# F_IN_CKT.net
KiCad netlist of a schematic drawn in Altium Designer
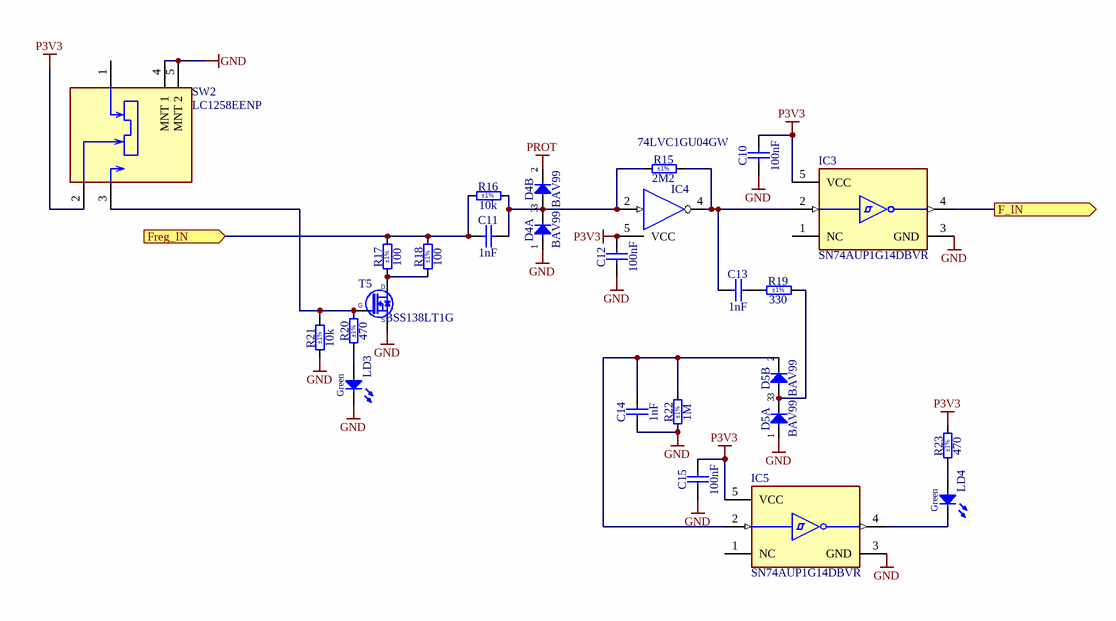
[diagram p0: F_IN_CKT.SchDoc]

(export (version "E")
  (design (tool "Eeschema 10.0.6"))
  (components
    (comp (ref "C10")
      (value "100nF")
      (footprint "CAPC1608X90N")
      (description "Non-polarised capacitor")
      (fields
        (field (name "PART NUMBER") "CC0603_100NF_100V_10%_X7R")
        (field (name "VOLTAGE") "100V")
        (field (name "AUTHOR") "CERN DEM JLC")
      )
      (libsource (lib "Capacitors") (part "Capacitor - non polarized"))
    )
    (comp (ref "C11")
      (value "1nF")
      (footprint "CAPC1608X90N")
      (description "Non-polarised capacitor")
      (fields
        (field (name "PART NUMBER") "CC0603_1NF_50V_1%_NP0")
        (field (name "VOLTAGE") "50V")
        (field (name "AUTHOR") "CERN DEM JLC")
      )
      (libsource (lib "Capacitors") (part "Capacitor - non polarized"))
    )
    (comp (ref "C12")
      (value "100nF")
      (footprint "CAPC1608X90N")
      (description "Non-polarised capacitor")
      (fields
        (field (name "PART NUMBER") "CC0603_100NF_100V_10%_X7R")
        (field (name "VOLTAGE") "100V")
        (field (name "AUTHOR") "CERN DEM JLC")
      )
      (libsource (lib "Capacitors") (part "Capacitor - non polarized"))
    )
    (comp (ref "C13")
      (value "1nF")
      (footprint "CAPC1608X90N")
      (description "Non-polarised capacitor")
      (fields
        (field (name "PART NUMBER") "CC0603_1NF_50V_1%_NP0")
        (field (name "VOLTAGE") "50V")
        (field (name "AUTHOR") "CERN DEM JLC")
      )
      (libsource (lib "Capacitors") (part "Capacitor - non polarized"))
    )
    (comp (ref "C14")
      (value "1nF")
      (footprint "CAPC1608X90N")
      (description "Non-polarised capacitor")
      (fields
        (field (name "PART NUMBER") "CC0603_1NF_50V_1%_NP0")
        (field (name "VOLTAGE") "50V")
        (field (name "AUTHOR") "CERN DEM JLC")
      )
      (libsource (lib "Capacitors") (part "Capacitor - non polarized"))
    )
    (comp (ref "C15")
      (value "100nF")
      (footprint "CAPC1608X90N")
      (description "Non-polarised capacitor")
      (fields
        (field (name "PART NUMBER") "CC0603_100NF_100V_10%_X7R")
        (field (name "VOLTAGE") "100V")
        (field (name "AUTHOR") "CERN DEM JLC")
      )
      (libsource (lib "Capacitors") (part "Capacitor - non polarized"))
    )
    (comp (ref "D4")
      (value "BAV99")
      (footprint "SOT95P240X110-3N")
      (description "Serial Diode")
      (fields
        (field (name "VOLTAGE") "70V")
        (field (name "POWER") "350mW")
        (field (name "AUTHOR") "CERN DEM JLC")
      )
      (libsource (lib "ICs And Semiconductors") (part "Diode x2 A1C3_A3C2"))
    )
    (comp (ref "D5")
      (value "BAV99")
      (footprint "SOT95P240X110-3N")
      (description "Serial Diode")
      (fields
        (field (name "VOLTAGE") "70V")
        (field (name "POWER") "350mW")
        (field (name "AUTHOR") "CERN DEM JLC")
      )
      (libsource (lib "ICs And Semiconductors") (part "Diode x2 A1C3_A3C2"))
    )
    (comp (ref "IC3")
      (value "SN74AUP1G14DBVR")
      (footprint "FP-DBV0005A-IPC_A")
      (description "IC INVERTER SCHMITT 1CH SOT23-5")
      (libsource (lib "Altium Content Vault") (part "d7d47fafed669226aeca1918140c228"))
    )
    (comp (ref "IC4")
      (value "74LVC1GU04GW")
      (footprint "SOT65P212X110-5N")
      (description "Single Inverter Buffer")
      (fields (field (name "MANUFACTURER") "NXP SEMICONDUCTORS") (field (name "AUTHOR") "CERN DEM JLC"))
      (libsource (lib "ICs And Semiconductors") (part "741G04"))
    )
    (comp (ref "IC5")
      (value "SN74AUP1G14DBVR")
      (footprint "FP-DBV0005A-IPC_A")
      (description "IC INVERTER SCHMITT 1CH SOT23-5")
      (libsource (lib "Altium Content Vault") (part "d7d47fafed669226aeca1918140c228"))
    )
    (comp (ref "LD3")
      (value "Green")
      (footprint "LED_AVAGO_HSME-C110")
      (description "LED Green 1C 2A")
      (fields
        (field (name "PART NUMBER") "LED_AVAGO_HSME-C110")
        (field (name "MANUFACTURER") "AVAGO TECHNOLOGIES")
        (field (name "AUTHOR") "CERN DEM JMW")
      )
      (libsource (lib "ICs And Semiconductors") (part "LED Green 1C 2A"))
    )
    (comp (ref "LD4")
      (value "Green")
      (footprint "LED_AVAGO_HSME-C110")
      (description "LED Green 1C 2A")
      (fields
        (field (name "PART NUMBER") "LED_AVAGO_HSME-C110")
        (field (name "MANUFACTURER") "AVAGO TECHNOLOGIES")
        (field (name "AUTHOR") "CERN DEM JMW")
      )
      (libsource (lib "ICs And Semiconductors") (part "LED Green 1C 2A"))
    )
    (comp (ref "R15")
      (value "2M2")
      (footprint "RESC1608X55N")
      (description "Resistor - 1%")
      (fields
        (field (name "TOLERANCE") "±1%")
        (field (name "PART NUMBER") "R0603_2M2_1%_0.1W_100PPM")
        (field (name "POWER") "0.1W")
        (field (name "AUTHOR") "CERN DEM JLC")
      )
      (libsource (lib "Resistors") (part "Resistor - 1%"))
    )
    (comp (ref "R16")
      (value "10k")
      (footprint "RESC1608X55N")
      (description "Resistor - 1%")
      (fields
        (field (name "TOLERANCE") "±1%")
        (field (name "PART NUMBER") "R0603_10K_1%_0.1W_100PPM")
        (field (name "POWER") "0.1W")
        (field (name "AUTHOR") "CERN DEM JLC")
      )
      (libsource (lib "Resistors") (part "Resistor - 1%"))
    )
    (comp (ref "R17")
      (value "100")
      (footprint "RESC1608X55N")
      (description "Resistor - 1%")
      (fields
        (field (name "TOLERANCE") "±1%")
        (field (name "PART NUMBER") "R0603_100R_1%_0.1W_100PPM")
        (field (name "POWER") "0.1W")
        (field (name "AUTHOR") "CERN DEM JLC")
      )
      (libsource (lib "Resistors") (part "Resistor - 1%"))
    )
    (comp (ref "R18")
      (value "100")
      (footprint "RESC1608X55N")
      (description "Resistor - 1%")
      (fields
        (field (name "TOLERANCE") "±1%")
        (field (name "PART NUMBER") "R0603_100R_1%_0.1W_100PPM")
        (field (name "POWER") "0.1W")
        (field (name "AUTHOR") "CERN DEM JLC")
      )
      (libsource (lib "Resistors") (part "Resistor - 1%"))
    )
    (comp (ref "R19")
      (value "330")
      (footprint "RESC1608X55N")
      (description "Resistor - 1%")
      (fields
        (field (name "TOLERANCE") "±1%")
        (field (name "PART NUMBER") "R0603_330R_1%_0.1W_100PPM")
        (field (name "POWER") "0.1W")
        (field (name "AUTHOR") "CERN DEM JLC")
      )
      (libsource (lib "Resistors") (part "Resistor - 1%"))
    )
    (comp (ref "R20")
      (value "470")
      (footprint "RESC1608X55N")
      (description "Resistor - 1%")
      (fields
        (field (name "TOLERANCE") "±1%")
        (field (name "PART NUMBER") "R0603_470R_1%_0.1W_100PPM")
        (field (name "POWER") "0.1W")
        (field (name "AUTHOR") "CERN DEM JLC")
      )
      (libsource (lib "Resistors") (part "Resistor - 1%"))
    )
    (comp (ref "R21")
      (value "10k")
      (footprint "RESC1608X55N")
      (description "Resistor - 1%")
      (fields
        (field (name "TOLERANCE") "±1%")
        (field (name "PART NUMBER") "R0603_10K_1%_0.1W_100PPM")
        (field (name "POWER") "0.1W")
        (field (name "AUTHOR") "CERN DEM JLC")
      )
      (libsource (lib "Resistors") (part "Resistor - 1%"))
    )
    (comp (ref "R22")
      (value "1M")
      (footprint "RESC1608X55N")
      (description "Resistor - 1%")
      (fields
        (field (name "TOLERANCE") "±1%")
        (field (name "PART NUMBER") "R0603_1M_1%_0.1W_100PPM")
        (field (name "POWER") "0.1W")
        (field (name "AUTHOR") "CERN DEM JLC")
      )
      (libsource (lib "Resistors") (part "Resistor - 1%"))
    )
    (comp (ref "R23")
      (value "470")
      (footprint "RESC1608X55N")
      (description "Resistor - 1%")
      (fields
        (field (name "TOLERANCE") "±1%")
        (field (name "PART NUMBER") "R0603_470R_1%_0.1W_100PPM")
        (field (name "POWER") "0.1W")
        (field (name "AUTHOR") "CERN DEM JLC")
      )
      (libsource (lib "Resistors") (part "Resistor - 1%"))
    )
    (comp (ref "SW2")
      (value "LC1258EENP")
      (footprint "FP-LC1258EENP-MFG")
      (description "SWITCH PUSHBUTTON SPDT 0.3A 30V")
      (fields
        (field (name "OCTOPART") "https://octopart.com/lc1258eenp-e-switch-1061525")
        (field (name "MANUFACTURER") "E-Switch")
      )
      (libsource (lib "Altium Content Vault") (part "0508c39cd0da6f0d1ad8893551ea0e6"))
    )
    (comp (ref "T5")
      (value "BSS138LT1G")
      (footprint "SOT95P240X110-3N")
      (description "N-CHANNEL MOSFET WITH DIODE")
      (fields
        (field (name "MANUFACTURER") "ON SEMICONDUCTOR")
        (field (name "MANUFACTURER PART NUMBER") "BSS138L")
        (field (name "AUTHOR") "CERN DEM JLC")
      )
      (libsource (lib "ICs And Semiconductors") (part "N-MOSFET-D 1G 2S 3D"))
    )
  )
  (nets
    (net (code "1") (name "/F_IN") (class "Default")
      (node (ref "IC3") (pin "4") (pinfunction "Y_4") (pintype "output"))
    )
    (net (code "2") (name "/Freg_IN") (class "Default")
      (node (ref "C11") (pin "1") (pinfunction "1_1") (pintype "passive"))
      (node (ref "R16") (pin "1") (pinfunction "1_1") (pintype "passive"))
      (node (ref "R17") (pin "2") (pinfunction "2_2") (pintype "passive"))
      (node (ref "R18") (pin "2") (pinfunction "2_2") (pintype "passive"))
    )
    (net (code "3") (name "GND") (class "Default")
      (node (ref "C10") (pin "1") (pinfunction "1_1") (pintype "passive"))
      (node (ref "C12") (pin "1") (pinfunction "1_1") (pintype "passive"))
      (node (ref "C14") (pin "1") (pinfunction "1_1") (pintype "passive"))
      (node (ref "C15") (pin "1") (pinfunction "1_1") (pintype "passive"))
      (node (ref "D4") (pin "1") (pinfunction "A_1") (pintype "passive"))
      (node (ref "D5") (pin "1") (pinfunction "A_1") (pintype "passive"))
      (node (ref "IC3") (pin "3") (pinfunction "GND_3") (pintype "power_in"))
      (node (ref "IC4") (pin "3") (pinfunction "GND_3") (pintype "power_in"))
      (node (ref "IC5") (pin "3") (pinfunction "GND_3") (pintype "power_in"))
      (node (ref "LD3") (pin "1") (pinfunction "C_1") (pintype "passive"))
      (node (ref "R21") (pin "1") (pinfunction "1_1") (pintype "passive"))
      (node (ref "R22") (pin "1") (pinfunction "1_1") (pintype "passive"))
      (node (ref "SW2") (pin "4") (pinfunction "MNT_1_4") (pintype "passive"))
      (node (ref "SW2") (pin "5") (pinfunction "MNT_2_5") (pintype "passive"))
      (node (ref "T5") (pin "2") (pinfunction "S_2") (pintype "passive"))
    )
    (net (code "4") (name "Net-(C13-Pad2)") (class "Default")
      (node (ref "C13") (pin "2") (pinfunction "2_2") (pintype "passive"))
      (node (ref "R19") (pin "1") (pinfunction "1_1") (pintype "passive"))
    )
    (net (code "5") (name "Net-(D4A-COMAC)") (class "Default")
      (node (ref "C11") (pin "2") (pinfunction "2_2") (pintype "passive"))
      (node (ref "D4") (pin "3") (pinfunction "COMAC_3") (pintype "passive"))
      (node (ref "IC4") (pin "2") (pinfunction "IN_2") (pintype "input"))
      (node (ref "R15") (pin "1") (pinfunction "1_1") (pintype "passive"))
      (node (ref "R16") (pin "2") (pinfunction "2_2") (pintype "passive"))
    )
    (net (code "6") (name "Net-(D5A-COMAC)") (class "Default")
      (node (ref "D5") (pin "3") (pinfunction "COMAC_3") (pintype "passive"))
      (node (ref "R19") (pin "2") (pinfunction "2_2") (pintype "passive"))
    )
    (net (code "7") (name "Net-(D5B-C)") (class "Default")
      (node (ref "C14") (pin "2") (pinfunction "2_2") (pintype "passive"))
      (node (ref "D5") (pin "2") (pinfunction "C_2") (pintype "passive"))
      (node (ref "IC5") (pin "2") (pinfunction "A_2") (pintype "input"))
      (node (ref "R22") (pin "2") (pinfunction "2_2") (pintype "passive"))
    )
    (net (code "8") (name "Net-(IC3-A)") (class "Default")
      (node (ref "C13") (pin "1") (pinfunction "1_1") (pintype "passive"))
      (node (ref "IC3") (pin "2") (pinfunction "A_2") (pintype "input"))
      (node (ref "IC4") (pin "4") (pinfunction "OUT_4") (pintype "open_collector"))
      (node (ref "R15") (pin "2") (pinfunction "2_2") (pintype "passive"))
    )
    (net (code "9") (name "Net-(IC5-Y)") (class "Default")
      (node (ref "IC5") (pin "4") (pinfunction "Y_4") (pintype "output"))
      (node (ref "LD4") (pin "1") (pinfunction "C_1") (pintype "passive"))
    )
    (net (code "10") (name "Net-(LD3-A)") (class "Default")
      (node (ref "LD3") (pin "2") (pinfunction "A_2") (pintype "passive"))
      (node (ref "R20") (pin "1") (pinfunction "1_1") (pintype "passive"))
    )
    (net (code "11") (name "Net-(LD4-A)") (class "Default")
      (node (ref "LD4") (pin "2") (pinfunction "A_2") (pintype "passive"))
      (node (ref "R23") (pin "1") (pinfunction "1_1") (pintype "passive"))
    )
    (net (code "12") (name "Net-(T5-D)") (class "Default")
      (node (ref "R17") (pin "1") (pinfunction "1_1") (pintype "passive"))
      (node (ref "R18") (pin "1") (pinfunction "1_1") (pintype "passive"))
      (node (ref "T5") (pin "3") (pinfunction "D_3") (pintype "passive"))
    )
    (net (code "13") (name "Net-(T5-G)") (class "Default")
      (node (ref "R20") (pin "2") (pinfunction "2_2") (pintype "passive"))
      (node (ref "R21") (pin "2") (pinfunction "2_2") (pintype "passive"))
      (node (ref "SW2") (pin "3") (pinfunction "3_3") (pintype "passive"))
      (node (ref "T5") (pin "1") (pinfunction "G_1") (pintype "passive"))
    )
    (net (code "14") (name "P3V3") (class "Default")
      (node (ref "C10") (pin "2") (pinfunction "2_2") (pintype "passive"))
      (node (ref "C12") (pin "2") (pinfunction "2_2") (pintype "passive"))
      (node (ref "C15") (pin "2") (pinfunction "2_2") (pintype "passive"))
      (node (ref "IC3") (pin "5") (pinfunction "VCC_5") (pintype "power_in"))
      (node (ref "IC4") (pin "5") (pinfunction "VCC_5") (pintype "power_in"))
      (node (ref "IC5") (pin "5") (pinfunction "VCC_5") (pintype "power_in"))
      (node (ref "R23") (pin "2") (pinfunction "2_2") (pintype "passive"))
      (node (ref "SW2") (pin "2") (pinfunction "2_2") (pintype "passive"))
    )
    (net (code "15") (name "PROT") (class "Default")
      (node (ref "D4") (pin "2") (pinfunction "C_2") (pintype "passive"))
    )
    (net (code "16") (name "unconnected-(IC3-NC-Pad1)") (class "Default")
      (node (ref "IC3") (pin "1") (pinfunction "NC_1") (pintype "passive"))
    )
    (net (code "17") (name "unconnected-(IC5-NC-Pad1)") (class "Default")
      (node (ref "IC5") (pin "1") (pinfunction "NC_1") (pintype "passive"))
    )
    (net (code "18") (name "unconnected-(SW2-Pad1)") (class "Default")
      (node (ref "SW2") (pin "1") (pinfunction "1_1") (pintype "passive"))
    )
  )
)
